# SD_Card.net
KiCad netlist of a schematic drawn in Altium Designer
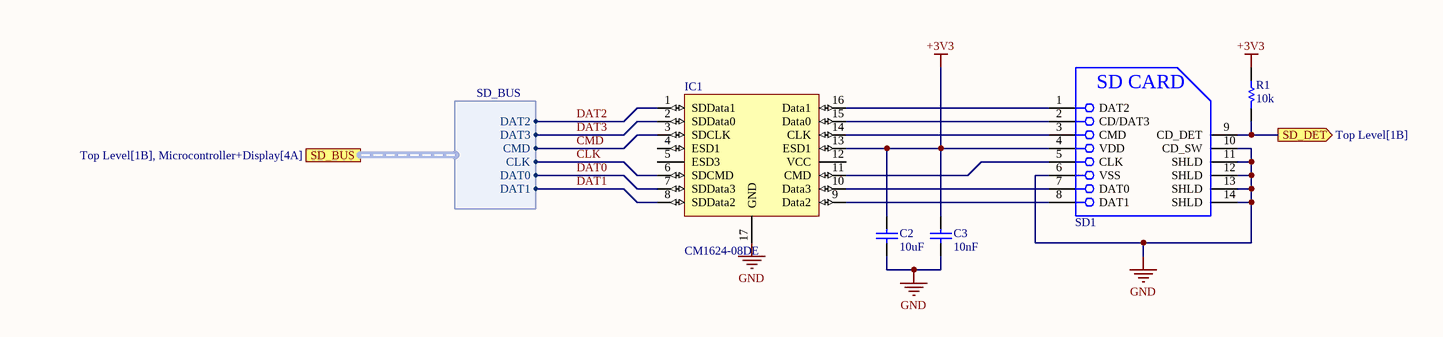
[diagram p0: SD Card.SchDoc]

(export (version "E")
  (design (tool "Eeschema 10.0.6"))
  (components
    (comp (ref "C2")
      (value "10uF")
      (footprint "CAPC2012X14N")
      (description "CAP CER 10UF 10V X5R 0805")
      (fields (field (name "VOLTAGE") "10V") (field (name "TOLERANCE") "10%"))
      (libsource (lib "Receiver_Library") (part "C0805C106K8PACTU"))
    )
    (comp (ref "C3")
      (value "10nF")
      (footprint "CAPC1608X10N")
      (description "Cap Ceramic 0.01uF 50V X7R 5% SMD 0603 125C Paper T/R")
      (fields (field (name "TOLERANCE") "5%") (field (name "Comment") "C0603C103J5RACTU"))
      (libsource (lib "Receiver_Library") (part "C0603C103J5RACTU"))
    )
    (comp (ref "IC1")
      (value "CM1624-08DE")
      (footprint "SON40P140X55_HS-17N")
      (description "EMI Filter Flat Style SMD T/R")
      (libsource (lib "Receiver_Library") (part "CM1624-08DE"))
    )
    (comp (ref "R1")
      (value "10k")
      (footprint "0603")
      (description "RES SMD 10K OHM 0.5% 1/10W 0603")
      (fields (field (name "Comment") "CRCW060310K0FKEA"))
      (libsource (lib "Receiver_Library") (part "CRCW060310K0FKEA"))
    )
    (comp (ref "SD1")
      (value "5027740891")
      (footprint "5027740891-Footprint-1")
      (description "MOLEX   502774-0891.   MEMORY CARD CONNECTOR, MICROSD, 8POS")
      (libsource (lib "Receiver_Library") (part "5027740891"))
    )
  )
  (nets
    (net (code "2") (name "+3V3") (class "Default")
      (node (ref "C2") (pin "2") (pinfunction "2_2") (pintype "passive"))
      (node (ref "C3") (pin "2") (pinfunction "2_2") (pintype "passive"))
      (node (ref "IC1") (pin "13") (pinfunction "ESD1_13") (pintype "bidirectional"))
      (node (ref "R1") (pin "1") (pinfunction "1_1") (pintype "passive"))
      (node (ref "SD1") (pin "4") (pinfunction "VDD_4") (pintype "passive"))
    )
    (net (code "3") (name "/CLK") (class "Default")
      (node (ref "IC1") (pin "6") (pinfunction "SDCMD_6") (pintype "bidirectional"))
    )
    (net (code "4") (name "/CMD") (class "Default")
      (node (ref "IC1") (pin "3") (pinfunction "SDCLK_3") (pintype "bidirectional"))
    )
    (net (code "5") (name "/DAT0") (class "Default")
      (node (ref "IC1") (pin "7") (pinfunction "SDData3_7") (pintype "bidirectional"))
    )
    (net (code "6") (name "/DAT1") (class "Default")
      (node (ref "IC1") (pin "8") (pinfunction "SDData2_8") (pintype "bidirectional"))
    )
    (net (code "7") (name "/DAT2") (class "Default")
      (node (ref "IC1") (pin "1") (pinfunction "SDData1_1") (pintype "bidirectional"))
    )
    (net (code "8") (name "/DAT3") (class "Default")
      (node (ref "IC1") (pin "2") (pinfunction "SDData0_2") (pintype "bidirectional"))
    )
    (net (code "9") (name "/SD_DET") (class "Default")
      (node (ref "R1") (pin "2") (pinfunction "2_2") (pintype "passive"))
      (node (ref "SD1") (pin "9") (pinfunction "CD_DET_9") (pintype "passive"))
    )
    (net (code "11") (name "GND") (class "Default")
      (node (ref "C2") (pin "1") (pinfunction "1_1") (pintype "passive"))
      (node (ref "C3") (pin "1") (pinfunction "1_1") (pintype "passive"))
      (node (ref "IC1") (pin "17") (pinfunction "GND_17") (pintype "power_in"))
      (node (ref "SD1") (pin "10") (pinfunction "CD_SW_10") (pintype "passive"))
      (node (ref "SD1") (pin "11") (pinfunction "SHLD_11") (pintype "passive"))
      (node (ref "SD1") (pin "12") (pinfunction "SHLD_12") (pintype "passive"))
      (node (ref "SD1") (pin "13") (pinfunction "SHLD_13") (pintype "passive"))
      (node (ref "SD1") (pin "14") (pinfunction "SHLD_14") (pintype "passive"))
      (node (ref "SD1") (pin "6") (pinfunction "VSS_6") (pintype "passive"))
    )
    (net (code "12") (name "Net-(IC1-CLK)") (class "Default")
      (node (ref "IC1") (pin "14") (pinfunction "CLK_14") (pintype "bidirectional"))
      (node (ref "SD1") (pin "3") (pinfunction "CMD_3") (pintype "passive"))
    )
    (net (code "13") (name "Net-(IC1-CMD)") (class "Default")
      (node (ref "IC1") (pin "11") (pinfunction "CMD_11") (pintype "bidirectional"))
      (node (ref "SD1") (pin "5") (pinfunction "CLK_5") (pintype "passive"))
    )
    (net (code "14") (name "Net-(IC1-Data0)") (class "Default")
      (node (ref "IC1") (pin "15") (pinfunction "Data0_15") (pintype "bidirectional"))
      (node (ref "SD1") (pin "2") (pinfunction "CD/DAT3_2") (pintype "passive"))
    )
    (net (code "15") (name "Net-(IC1-Data1)") (class "Default")
      (node (ref "IC1") (pin "16") (pinfunction "Data1_16") (pintype "bidirectional"))
      (node (ref "SD1") (pin "1") (pinfunction "DAT2_1") (pintype "passive"))
    )
    (net (code "16") (name "Net-(IC1-Data2)") (class "Default")
      (node (ref "IC1") (pin "9") (pinfunction "Data2_9") (pintype "bidirectional"))
      (node (ref "SD1") (pin "8") (pinfunction "DAT1_8") (pintype "passive"))
    )
    (net (code "17") (name "Net-(IC1-Data3)") (class "Default")
      (node (ref "IC1") (pin "10") (pinfunction "Data3_10") (pintype "bidirectional"))
      (node (ref "SD1") (pin "7") (pinfunction "DAT0_7") (pintype "passive"))
    )
    (net (code "18") (name "unconnected-(IC1-ESD1-Pad4)") (class "Default")
      (node (ref "IC1") (pin "4") (pinfunction "ESD1_4") (pintype "bidirectional"))
    )
    (net (code "19") (name "unconnected-(IC1-ESD3-Pad5)") (class "Default")
      (node (ref "IC1") (pin "5") (pinfunction "ESD3_5") (pintype "passive"))
    )
    (net (code "20") (name "unconnected-(IC1-VCC-Pad12)") (class "Default")
      (node (ref "IC1") (pin "12") (pinfunction "VCC_12") (pintype "power_in"))
    )
  )
)
